# ExtensionV1.net
KiCad netlist of a schematic drawn in EAGLE
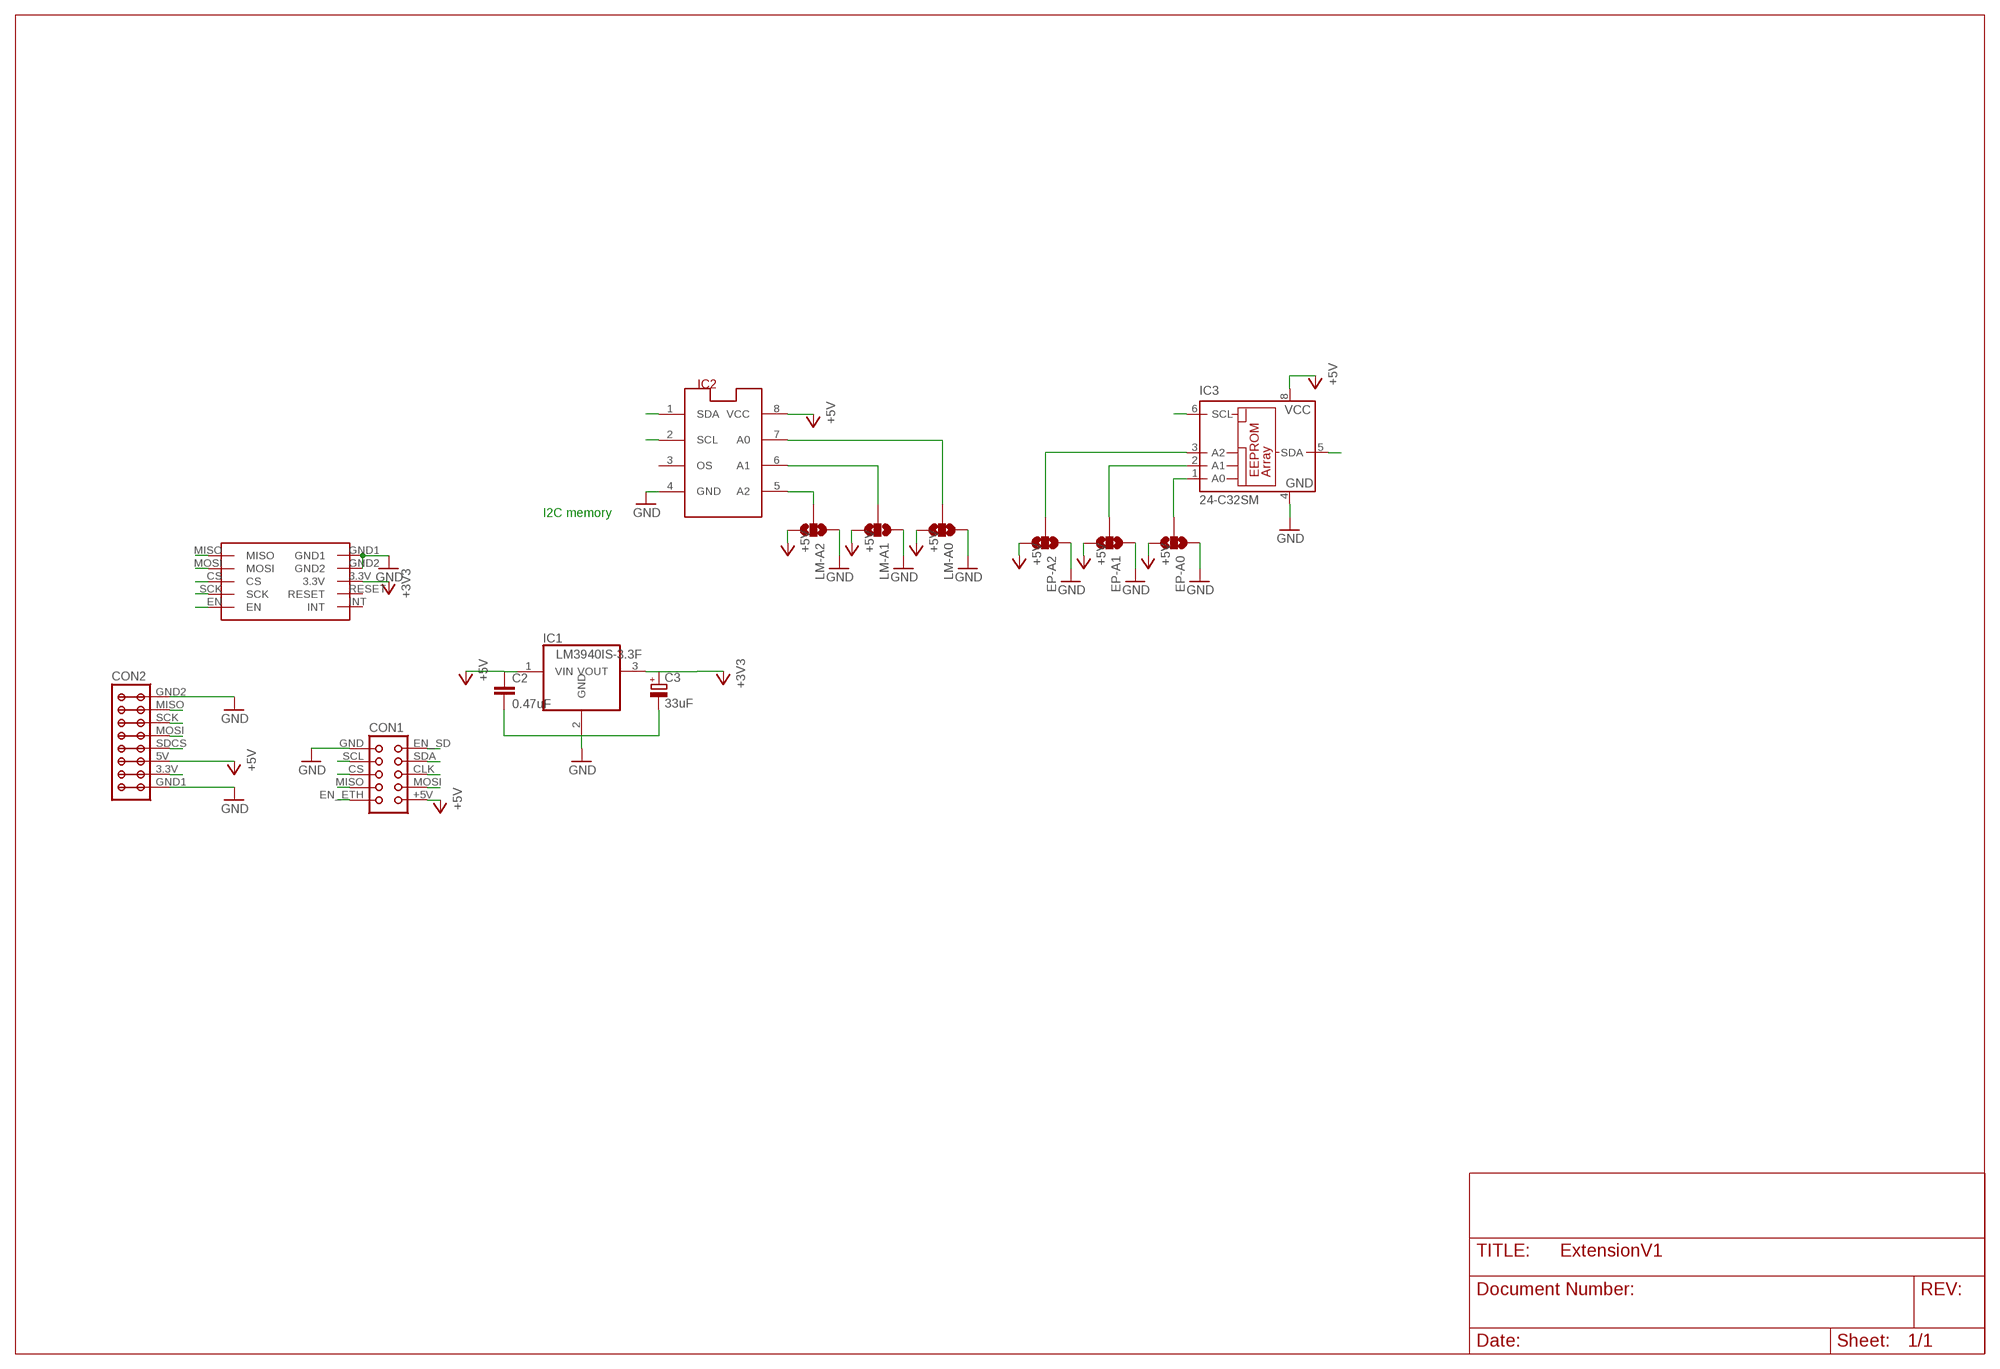
[diagram p0: schematic, sheet 1]

(export (version "E")
  (design (tool "Eeschema 10.0.6"))
  (components
    (comp (ref "C2")
      (value "0.47uF")
      (footprint "eagle-import:C1206")
      (libsource (lib "eagle-import") (part "C-EUC1206"))
    )
    (comp (ref "C3")
      (value "33uF")
      (footprint "eagle-import:E3,5-8")
      (libsource (lib "eagle-import") (part "CPOL-EUE3.5-8"))
    )
    (comp (ref "CON1")
      (value "CON10EXT")
      (footprint "eagle-import:CON10EXT")
      (libsource (lib "eagle-import") (part "CON10EXT"))
    )
    (comp (ref "CON2")
      (value "SD-CARD-EXTENSION")
      (footprint "eagle-import:SD-CARD")
      (libsource (lib "eagle-import") (part "SD-CARD-EXTENSION"))
    )
    (comp (ref "EP-A0")
      (value "SOLDERJUMPER_2WAY")
      (footprint "eagle-import:1206-SWITCH")
      (libsource (lib "eagle-import") (part "SOLDERJUMPER_2WAY"))
    )
    (comp (ref "EP-A1")
      (value "SOLDERJUMPER_2WAY")
      (footprint "eagle-import:1206-SWITCH")
      (libsource (lib "eagle-import") (part "SOLDERJUMPER_2WAY"))
    )
    (comp (ref "EP-A2")
      (value "SOLDERJUMPER_2WAY")
      (footprint "eagle-import:1206-SWITCH")
      (libsource (lib "eagle-import") (part "SOLDERJUMPER_2WAY"))
    )
    (comp (ref "IC1")
      (value "LM3940IS-3.3F")
      (footprint "eagle-import:DD-3")
      (fields (field (name "MF") "TEXAS INSTRUMENTS") (field (name "MPN") "REG1117FAKTTT"))
      (libsource (lib "eagle-import") (part "LM3940IS-3.3F"))
    )
    (comp (ref "IC2")
      (value "LM75_ICN")
      (footprint "eagle-import:SO8_LM75")
      (libsource (lib "eagle-import") (part "LM75_ICN"))
    )
    (comp (ref "IC3")
      (value "24-C32SM")
      (footprint "eagle-import:SO-08M")
      (fields (field (name "MPN") "M24C32-WMN6P"))
      (libsource (lib "eagle-import") (part "24-SMC32"))
    )
    (comp (ref "LM-A0")
      (value "SOLDERJUMPER_2WAY")
      (footprint "eagle-import:1206-SWITCH")
      (libsource (lib "eagle-import") (part "SOLDERJUMPER_2WAY"))
    )
    (comp (ref "LM-A1")
      (value "SOLDERJUMPER_2WAY")
      (footprint "eagle-import:1206-SWITCH")
      (libsource (lib "eagle-import") (part "SOLDERJUMPER_2WAY"))
    )
    (comp (ref "LM-A2")
      (value "SOLDERJUMPER_2WAY")
      (footprint "eagle-import:1206-SWITCH")
      (libsource (lib "eagle-import") (part "SOLDERJUMPER_2WAY"))
    )
    (comp (ref "U$1")
      (value "W5100")
      (footprint "eagle-import:W5100")
      (libsource (lib "eagle-import") (part "W5100"))
    )
  )
  (nets
    (net (code "1") (name "+3V3") (class "Default")
      (node (ref "C3") (pin "+") (pinfunction "+_+") (pintype "passive"))
      (node (ref "IC1") (pin "3") (pinfunction "VOUT_3") (pintype "output"))
      (node (ref "U$1") (pin "3.3V") (pinfunction "3.3V_3.3V") (pintype "power_in"))
    )
    (net (code "2") (name "+5V") (class "Default")
      (node (ref "C2") (pin "1") (pinfunction "1_1") (pintype "passive"))
      (node (ref "CON1") (pin "+5V") (pinfunction "1_+5V") (pintype "passive"))
      (node (ref "CON2") (pin "5V") (pinfunction "5V_5V") (pintype "passive"))
      (node (ref "EP-A0") (pin "3") (pinfunction "3_3") (pintype "passive"))
      (node (ref "EP-A1") (pin "3") (pinfunction "3_3") (pintype "passive"))
      (node (ref "EP-A2") (pin "3") (pinfunction "3_3") (pintype "passive"))
      (node (ref "IC1") (pin "1") (pinfunction "VIN_1") (pintype "input"))
      (node (ref "IC2") (pin "8") (pinfunction "VCC_8") (pintype "power_in"))
      (node (ref "IC3") (pin "8") (pinfunction "VCC_8") (pintype "power_in"))
      (node (ref "LM-A0") (pin "3") (pinfunction "3_3") (pintype "passive"))
      (node (ref "LM-A1") (pin "3") (pinfunction "3_3") (pintype "passive"))
      (node (ref "LM-A2") (pin "3") (pinfunction "3_3") (pintype "passive"))
    )
    (net (code "3") (name "/CLK") (class "Default")
      (node (ref "CON1") (pin "CLK") (pinfunction "5_CLK") (pintype "passive"))
      (node (ref "CON2") (pin "SCK") (pinfunction "SCK_SCK") (pintype "passive"))
      (node (ref "U$1") (pin "SCK") (pinfunction "SCK_SCK") (pintype "bidirectional"))
    )
    (net (code "4") (name "/EN_ETH") (class "Default")
      (node (ref "CON1") (pin "EN_ETH") (pinfunction "2_EN_ETH") (pintype "passive"))
      (node (ref "U$1") (pin "EN") (pinfunction "EN_EN") (pintype "bidirectional"))
    )
    (net (code "5") (name "/EN_SD") (class "Default")
      (node (ref "CON1") (pin "EN_SD") (pinfunction "9_EN_SD") (pintype "passive"))
      (node (ref "CON2") (pin "SDCS") (pinfunction "SDCS_SDCS") (pintype "passive"))
    )
    (net (code "6") (name "/MISO") (class "Default")
      (node (ref "CON2") (pin "MISO") (pinfunction "MISO_MISO") (pintype "passive"))
      (node (ref "U$1") (pin "MISO") (pinfunction "MISO_MISO") (pintype "bidirectional"))
    )
    (net (code "7") (name "/MOSI") (class "Default")
      (node (ref "CON1") (pin "MOSI") (pinfunction "3_MOSI") (pintype "passive"))
      (node (ref "CON2") (pin "MOSI") (pinfunction "MOSI_MOSI") (pintype "passive"))
      (node (ref "U$1") (pin "MOSI") (pinfunction "MOSI_MOSI") (pintype "bidirectional"))
    )
    (net (code "8") (name "/SCL") (class "Default")
      (node (ref "CON1") (pin "SCL") (pinfunction "8_SCL") (pintype "passive"))
      (node (ref "IC2") (pin "2") (pinfunction "SCL_2") (pintype "bidirectional"))
      (node (ref "IC3") (pin "6") (pinfunction "SCL_6") (pintype "input"))
    )
    (net (code "9") (name "/SDA") (class "Default")
      (node (ref "CON1") (pin "SDA") (pinfunction "7_SDA") (pintype "passive"))
      (node (ref "IC2") (pin "1") (pinfunction "SDA_1") (pintype "bidirectional"))
      (node (ref "IC3") (pin "5") (pinfunction "SDA_5") (pintype "bidirectional"))
    )
    (net (code "10") (name "GND") (class "Default")
      (node (ref "C2") (pin "2") (pinfunction "2_2") (pintype "passive"))
      (node (ref "C3") (pin "-") (pinfunction "-_-") (pintype "passive"))
      (node (ref "CON1") (pin "GND") (pinfunction "10_GND") (pintype "passive"))
      (node (ref "CON2") (pin "GND1") (pinfunction "GND1_GND1") (pintype "passive"))
      (node (ref "CON2") (pin "GND2") (pinfunction "GND2_GND2") (pintype "passive"))
      (node (ref "EP-A0") (pin "1") (pinfunction "1_1") (pintype "passive"))
      (node (ref "EP-A1") (pin "1") (pinfunction "1_1") (pintype "passive"))
      (node (ref "EP-A2") (pin "1") (pinfunction "1_1") (pintype "passive"))
      (node (ref "IC1") (pin "2") (pinfunction "GND_2") (pintype "power_in"))
      (node (ref "IC2") (pin "4") (pinfunction "GND_4") (pintype "power_in"))
      (node (ref "IC3") (pin "4") (pinfunction "GND_4") (pintype "power_in"))
      (node (ref "LM-A0") (pin "1") (pinfunction "1_1") (pintype "passive"))
      (node (ref "LM-A1") (pin "1") (pinfunction "1_1") (pintype "passive"))
      (node (ref "LM-A2") (pin "1") (pinfunction "1_1") (pintype "passive"))
      (node (ref "U$1") (pin "GND1") (pinfunction "GND1_GND1") (pintype "bidirectional"))
      (node (ref "U$1") (pin "GND2") (pinfunction "GND2_GND2") (pintype "bidirectional"))
    )
    (net (code "11") (name "Net-(IC2-A0)") (class "Default")
      (node (ref "IC2") (pin "7") (pinfunction "A0_7") (pintype "input"))
      (node (ref "LM-A0") (pin "2") (pinfunction "2_2") (pintype "passive"))
    )
    (net (code "12") (name "Net-(IC2-A1)") (class "Default")
      (node (ref "IC2") (pin "6") (pinfunction "A1_6") (pintype "input"))
      (node (ref "LM-A1") (pin "2") (pinfunction "2_2") (pintype "passive"))
    )
    (net (code "13") (name "Net-(IC2-A2)") (class "Default")
      (node (ref "IC2") (pin "5") (pinfunction "A2_5") (pintype "input"))
      (node (ref "LM-A2") (pin "2") (pinfunction "2_2") (pintype "passive"))
    )
    (net (code "14") (name "Net-(IC3-A0)") (class "Default")
      (node (ref "EP-A0") (pin "2") (pinfunction "2_2") (pintype "passive"))
      (node (ref "IC3") (pin "1") (pinfunction "A0_1") (pintype "input"))
    )
    (net (code "15") (name "Net-(IC3-A1)") (class "Default")
      (node (ref "EP-A1") (pin "2") (pinfunction "2_2") (pintype "passive"))
      (node (ref "IC3") (pin "2") (pinfunction "A1_2") (pintype "input"))
    )
    (net (code "16") (name "Net-(IC3-A2)") (class "Default")
      (node (ref "EP-A2") (pin "2") (pinfunction "2_2") (pintype "passive"))
      (node (ref "IC3") (pin "3") (pinfunction "A2_3") (pintype "input"))
    )
    (net (code "17") (name "unconnected-(CON1-4-PadMISO)") (class "Default")
      (node (ref "CON1") (pin "MISO") (pinfunction "4_MISO") (pintype "passive"))
    )
    (net (code "18") (name "unconnected-(CON1-6-PadCS)") (class "Default")
      (node (ref "CON1") (pin "CS") (pinfunction "6_CS") (pintype "passive"))
    )
    (net (code "19") (name "unconnected-(CON2-Pad3.3V)") (class "Default")
      (node (ref "CON2") (pin "3.3V") (pinfunction "3.3V_3.3V") (pintype "passive"))
    )
    (net (code "20") (name "unconnected-(IC2-OS-Pad3)") (class "Default")
      (node (ref "IC2") (pin "3") (pinfunction "OS_3") (pintype "output"))
    )
    (net (code "21") (name "unconnected-(U$1-PadCS)") (class "Default")
      (node (ref "U$1") (pin "CS") (pinfunction "CS_CS") (pintype "bidirectional"))
    )
    (net (code "22") (name "unconnected-(U$1-PadINT)") (class "Default")
      (node (ref "U$1") (pin "INT") (pinfunction "INT_INT") (pintype "bidirectional"))
    )
    (net (code "23") (name "unconnected-(U$1-PadRESET)") (class "Default")
      (node (ref "U$1") (pin "RESET") (pinfunction "RESET_RESET") (pintype "bidirectional"))
    )
  )
)
